# SparkFun_Buck_Regulator_AP63357DV-7_Buck.net
KiCad netlist of a schematic drawn in EAGLE
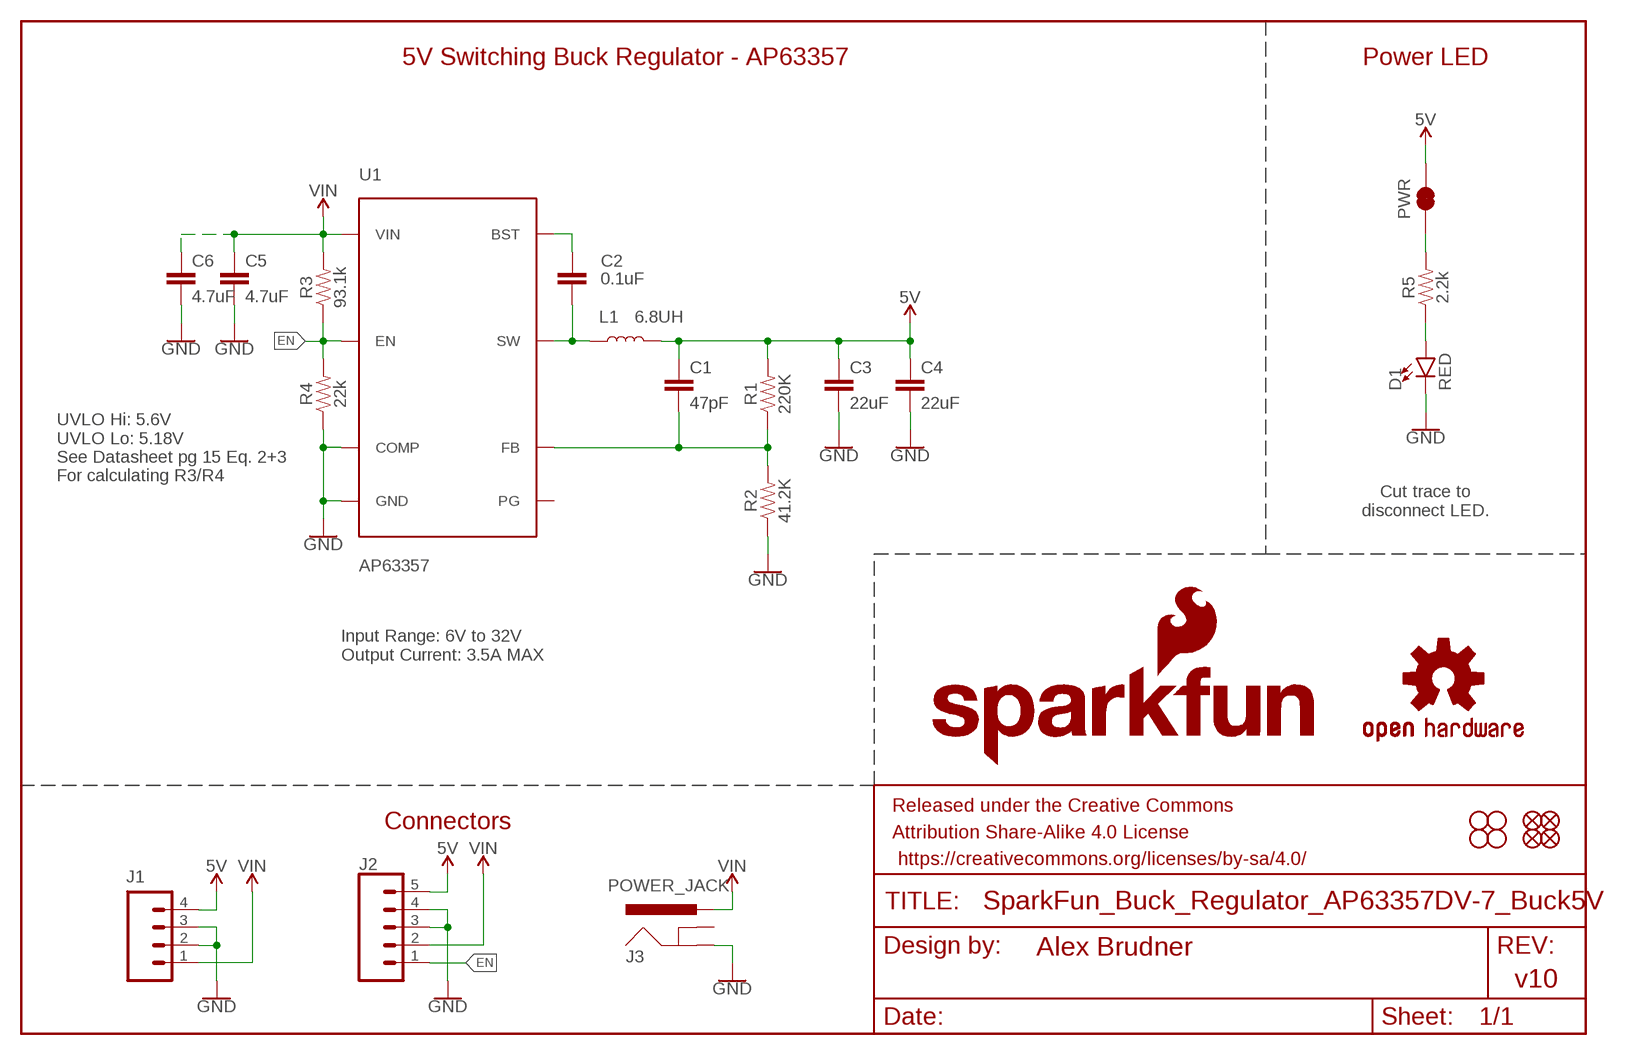
[diagram p0: schematic, sheet 1]

(export (version "E")
  (design (tool "Eeschema 10.0.6"))
  (components
    (comp (ref "C1")
      (value "47pF")
      (footprint "eagle-import:0402-TIGHT")
      (libsource (lib "eagle-import") (part "47PF-0402_TIGHT-25V-5%-X7R"))
    )
    (comp (ref "C2")
      (value "0.1uF")
      (footprint "eagle-import:0402-TIGHT")
      (libsource (lib "eagle-import") (part "0.1UF-0402T-16V-10%"))
    )
    (comp (ref "C3")
      (value "22uF")
      (footprint "eagle-import:0805")
      (libsource (lib "eagle-import") (part "22UF-0805-16V-20%"))
    )
    (comp (ref "C4")
      (value "22uF")
      (footprint "eagle-import:0805")
      (libsource (lib "eagle-import") (part "22UF-0805-16V-20%"))
    )
    (comp (ref "C5")
      (value "4.7uF")
      (footprint "eagle-import:0805")
      (libsource (lib "eagle-import") (part "4.7UF-0805-50V-(10%)"))
    )
    (comp (ref "C6")
      (value "4.7uF")
      (footprint "eagle-import:0805")
      (libsource (lib "eagle-import") (part "4.7UF-0805-50V-(10%)"))
    )
    (comp (ref "D1")
      (value "RED")
      (footprint "eagle-import:LED-0603")
      (libsource (lib "eagle-import") (part "LED-RED0603"))
    )
    (comp (ref "FD1")
      (value "FIDUCIALUFIDUCIAL")
      (footprint "eagle-import:FIDUCIAL-MICRO")
      (libsource (lib "eagle-import") (part "FIDUCIALUFIDUCIAL"))
    )
    (comp (ref "FD2")
      (value "FIDUCIALUFIDUCIAL")
      (footprint "eagle-import:FIDUCIAL-MICRO")
      (libsource (lib "eagle-import") (part "FIDUCIALUFIDUCIAL"))
    )
    (comp (ref "FD3")
      (value "FIDUCIALUFIDUCIAL")
      (footprint "eagle-import:FIDUCIAL-MICRO")
      (libsource (lib "eagle-import") (part "FIDUCIALUFIDUCIAL"))
    )
    (comp (ref "FD4")
      (value "FIDUCIALUFIDUCIAL")
      (footprint "eagle-import:FIDUCIAL-MICRO")
      (libsource (lib "eagle-import") (part "FIDUCIALUFIDUCIAL"))
    )
    (comp (ref "FRAME1")
      (value "FRAME-LEDGER")
      (footprint "eagle-import:CREATIVE_COMMONS")
      (fields (field (name "DESIGNER") "Alex Brudner") (field (name "REV") "v10"))
      (libsource (lib "eagle-import") (part "FRAME-LEDGER"))
    )
    (comp (ref "H1")
      (value "STAND-OFF")
      (footprint "eagle-import:STAND-OFF")
      (libsource (lib "eagle-import") (part "STAND-OFF"))
    )
    (comp (ref "H2")
      (value "STAND-OFF")
      (footprint "eagle-import:STAND-OFF")
      (libsource (lib "eagle-import") (part "STAND-OFF"))
    )
    (comp (ref "H3")
      (value "STAND-OFF")
      (footprint "eagle-import:STAND-OFF")
      (libsource (lib "eagle-import") (part "STAND-OFF"))
    )
    (comp (ref "H4")
      (value "STAND-OFF")
      (footprint "eagle-import:STAND-OFF")
      (libsource (lib "eagle-import") (part "STAND-OFF"))
    )
    (comp (ref "J1")
      (value "CONN_04SCREW")
      (footprint "eagle-import:SCREWTERMINAL-3.5MM-4")
      (libsource (lib "eagle-import") (part "CONN_04SCREW"))
    )
    (comp (ref "J2")
      (value "CONN_05NO_SILK")
      (footprint "eagle-import:1X05_NO_SILK")
      (libsource (lib "eagle-import") (part "CONN_05NO_SILK"))
    )
    (comp (ref "J3")
      (value "POWER_JACK")
      (footprint "eagle-import:POWER_JACK_PTH_SLOT_NO_OVRHNG_SILK")
      (libsource (lib "eagle-import") (part "POWER_JACKPOWER_JACK_SLOT_NO_SILK_OVRHNG"))
    )
    (comp (ref "L1")
      (value "6.8UH")
      (footprint "eagle-import:07A7_6U8H")
      (libsource (lib "eagle-import") (part "6.8UH"))
    )
    (comp (ref "LOGO1")
      (value "OSHW-LOGOMINI")
      (footprint "eagle-import:OSHW-LOGO-MINI")
      (libsource (lib "eagle-import") (part "OSHW-LOGOMINI"))
    )
    (comp (ref "LOGO2")
      (value "SFE_LOGO_NAME_FLAME.1_INCH")
      (footprint "eagle-import:SFE_LOGO_NAME_FLAME_.1")
      (libsource (lib "eagle-import") (part "SFE_LOGO_NAME_FLAME.1_INCH"))
    )
    (comp (ref "PWR")
      (value "JUMPER-SMT_2_NC_TRACE_SILK")
      (footprint "eagle-import:SMT-JUMPER_2_NC_TRACE_SILK")
      (libsource (lib "eagle-import") (part "JUMPER-SMT_2_NC_TRACE_SILK"))
    )
    (comp (ref "R1")
      (value "220K")
      (footprint "eagle-import:0402-TIGHT")
      (libsource (lib "eagle-import") (part "220KOHM-0402T-1/16W-1%"))
    )
    (comp (ref "R2")
      (value "41.2K")
      (footprint "eagle-import:0402-TIGHT")
      (libsource (lib "eagle-import") (part "41.2KOHM-0402-1/16W-1%(41.2KOHM)"))
    )
    (comp (ref "R3")
      (value "93.1k")
      (footprint "eagle-import:0402-TIGHT")
      (libsource (lib "eagle-import") (part "93.1KOHM-0402-1/16W-1%(93.1KOHM)"))
    )
    (comp (ref "R4")
      (value "22k")
      (footprint "eagle-import:0402-TIGHT")
      (libsource (lib "eagle-import") (part "22KOHM-0402_TIGHT-1/10W-1%"))
    )
    (comp (ref "R5")
      (value "2.2k")
      (footprint "eagle-import:0402-TIGHT")
      (libsource (lib "eagle-import") (part "2.2KOHM-0402T-1/16W-1%"))
    )
    (comp (ref "U1")
      (value "AP63357")
      (footprint "eagle-import:V-DFN3020-13")
      (libsource (lib "eagle-import") (part "AP63357"))
    )
  )
  (nets
    (net (code "1") (name "5V") (class "Default")
      (node (ref "C1") (pin "1") (pinfunction "1_1") (pintype "passive"))
      (node (ref "C3") (pin "1") (pinfunction "1_1") (pintype "passive"))
      (node (ref "C4") (pin "1") (pinfunction "1_1") (pintype "passive"))
      (node (ref "J1") (pin "4") (pinfunction "4_4") (pintype "passive"))
      (node (ref "J2") (pin "5") (pinfunction "5_5") (pintype "passive"))
      (node (ref "L1") (pin "P$2") (pinfunction "2_P$2") (pintype "passive"))
      (node (ref "PWR") (pin "2") (pinfunction "2_2") (pintype "passive"))
      (node (ref "R1") (pin "2") (pinfunction "2_2") (pintype "passive"))
    )
    (net (code "2") (name "EN") (class "Default")
      (node (ref "J2") (pin "1") (pinfunction "1_1") (pintype "passive"))
      (node (ref "R3") (pin "1") (pinfunction "1_1") (pintype "passive"))
      (node (ref "R4") (pin "2") (pinfunction "2_2") (pintype "passive"))
      (node (ref "U1") (pin "P$2") (pinfunction "EN_P$2") (pintype "bidirectional"))
    )
    (net (code "3") (name "GND") (class "Default")
      (node (ref "C3") (pin "2") (pinfunction "2_2") (pintype "passive"))
      (node (ref "C4") (pin "2") (pinfunction "2_2") (pintype "passive"))
      (node (ref "C5") (pin "2") (pinfunction "2_2") (pintype "passive"))
      (node (ref "C6") (pin "2") (pinfunction "2_2") (pintype "passive"))
      (node (ref "D1") (pin "C") (pinfunction "C_C") (pintype "passive"))
      (node (ref "J1") (pin "2") (pinfunction "2_2") (pintype "passive"))
      (node (ref "J1") (pin "3") (pinfunction "3_3") (pintype "passive"))
      (node (ref "J2") (pin "3") (pinfunction "3_3") (pintype "passive"))
      (node (ref "J2") (pin "4") (pinfunction "4_4") (pintype "passive"))
      (node (ref "J3") (pin "GND") (pinfunction "GND_GND") (pintype "bidirectional"))
      (node (ref "R2") (pin "1") (pinfunction "1_1") (pintype "passive"))
      (node (ref "R4") (pin "1") (pinfunction "1_1") (pintype "passive"))
      (node (ref "U1") (pin "P$4") (pinfunction "COMP_P$4") (pintype "bidirectional"))
      (node (ref "U1") (pin "P$8") (pinfunction "GND_P$8") (pintype "power_in"))
    )
    (net (code "4") (name "Net-(D1-PadA)") (class "Default")
      (node (ref "D1") (pin "A") (pinfunction "A_A") (pintype "passive"))
      (node (ref "R5") (pin "1") (pinfunction "1_1") (pintype "passive"))
    )
    (net (code "5") (name "Net-(L1-1)") (class "Default")
      (node (ref "C2") (pin "2") (pinfunction "2_2") (pintype "passive"))
      (node (ref "L1") (pin "P$1") (pinfunction "1_P$1") (pintype "passive"))
      (node (ref "U1") (pin "P$7") (pinfunction "SW_P$7") (pintype "power_in"))
      (node (ref "U1") (pin "P$9") (pinfunction "SW_P$9") (pintype "power_in"))
    )
    (net (code "6") (name "Net-(PWR-Pad1)") (class "Default")
      (node (ref "PWR") (pin "1") (pinfunction "1_1") (pintype "passive"))
      (node (ref "R5") (pin "2") (pinfunction "2_2") (pintype "passive"))
    )
    (net (code "7") (name "Net-(U1-BST)") (class "Default")
      (node (ref "C2") (pin "1") (pinfunction "1_1") (pintype "passive"))
      (node (ref "U1") (pin "P$6") (pinfunction "BST_P$6") (pintype "bidirectional"))
    )
    (net (code "8") (name "Net-(U1-FB)") (class "Default")
      (node (ref "C1") (pin "2") (pinfunction "2_2") (pintype "passive"))
      (node (ref "R1") (pin "1") (pinfunction "1_1") (pintype "passive"))
      (node (ref "R2") (pin "2") (pinfunction "2_2") (pintype "passive"))
      (node (ref "U1") (pin "P$3") (pinfunction "FB_P$3") (pintype "input"))
    )
    (net (code "9") (name "VIN") (class "Default")
      (node (ref "C5") (pin "1") (pinfunction "1_1") (pintype "passive"))
      (node (ref "C6") (pin "1") (pinfunction "1_1") (pintype "passive"))
      (node (ref "J1") (pin "1") (pinfunction "1_1") (pintype "passive"))
      (node (ref "J2") (pin "2") (pinfunction "2_2") (pintype "passive"))
      (node (ref "J3") (pin "PWR") (pinfunction "PWR_PWR") (pintype "bidirectional"))
      (node (ref "R3") (pin "2") (pinfunction "2_2") (pintype "passive"))
      (node (ref "U1") (pin "P$1") (pinfunction "VIN_P$1") (pintype "power_in"))
    )
    (net (code "10") (name "unconnected-(J3-PadGNDBREAK)") (class "Default")
      (node (ref "J3") (pin "GNDBREAK") (pinfunction "GNDBREAK_GNDBREAK") (pintype "bidirectional"))
    )
    (net (code "11") (name "unconnected-(U1-PG-PadP$5)") (class "Default")
      (node (ref "U1") (pin "P$5") (pinfunction "PG_P$5") (pintype "output"))
    )
  )
)
